# SilovaCastV2.net
KiCad netlist of a schematic drawn in EAGLE
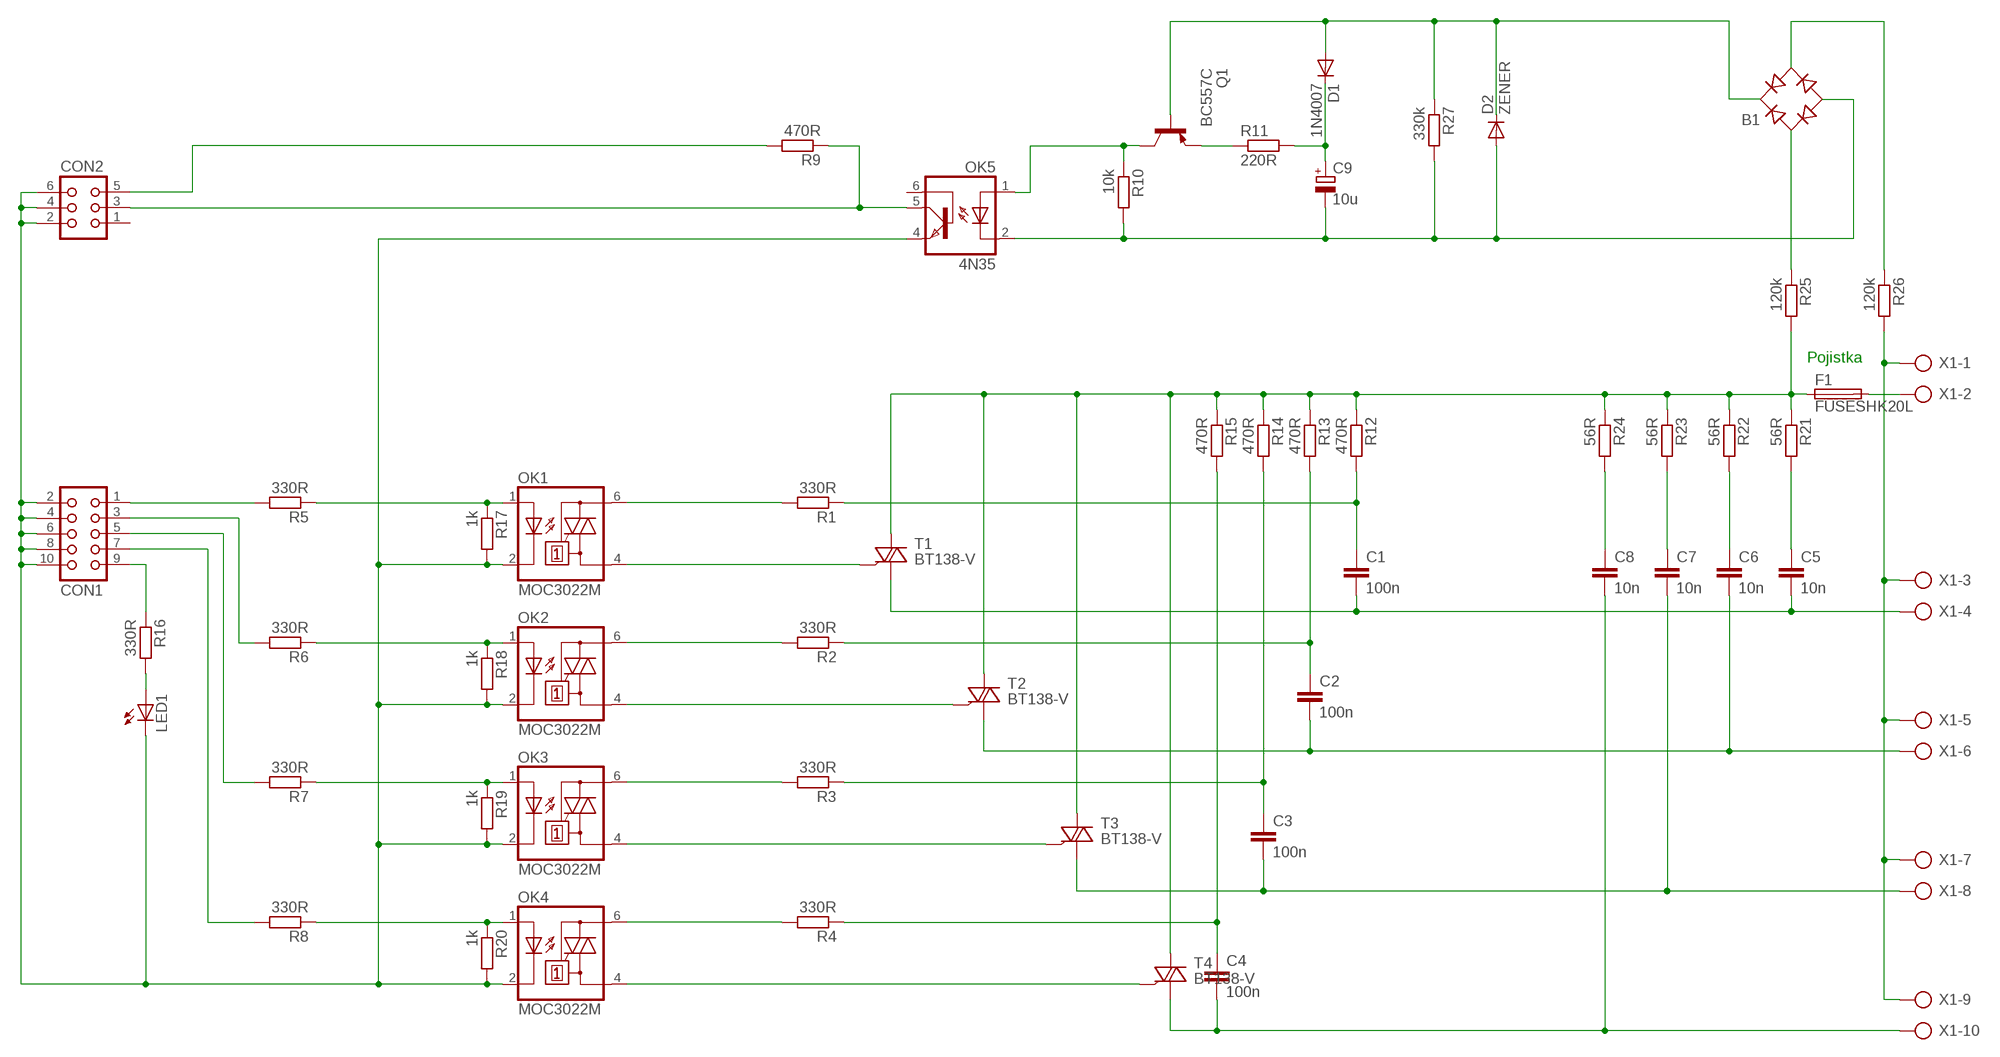
[diagram p0: schematic, sheet 1]

(export (version "E")
  (design (tool "Eeschema 10.0.6"))
  (components
    (comp (ref "B1")
      (value "RB1A")
      (footprint "eagle-import:RB1A")
      (libsource (lib "eagle-import") (part "RB1A"))
    )
    (comp (ref "C1")
      (value "100n")
      (footprint "eagle-import:C7.5B6")
      (libsource (lib "eagle-import") (part "C7.5/6"))
    )
    (comp (ref "C2")
      (value "100n")
      (footprint "eagle-import:C7.5B6")
      (libsource (lib "eagle-import") (part "C7.5/6"))
    )
    (comp (ref "C3")
      (value "100n")
      (footprint "eagle-import:C7.5B6")
      (libsource (lib "eagle-import") (part "C7.5/6"))
    )
    (comp (ref "C4")
      (value "100n")
      (footprint "eagle-import:C7.5B6")
      (libsource (lib "eagle-import") (part "C7.5/6"))
    )
    (comp (ref "C5")
      (value "10n")
      (footprint "eagle-import:C7.5B6")
      (libsource (lib "eagle-import") (part "C7.5/6"))
    )
    (comp (ref "C6")
      (value "10n")
      (footprint "eagle-import:C7.5B6")
      (libsource (lib "eagle-import") (part "C7.5/6"))
    )
    (comp (ref "C7")
      (value "10n")
      (footprint "eagle-import:C7.5B6")
      (libsource (lib "eagle-import") (part "C7.5/6"))
    )
    (comp (ref "C8")
      (value "10n")
      (footprint "eagle-import:C7.5B6")
      (libsource (lib "eagle-import") (part "C7.5/6"))
    )
    (comp (ref "C9")
      (value "10u")
      (footprint "eagle-import:E3,5-8")
      (libsource (lib "eagle-import") (part "CPOL-EUE3.5-8"))
    )
    (comp (ref "CON1")
      (value "CON10")
      (footprint "eagle-import:CON10")
      (libsource (lib "eagle-import") (part "CON10"))
    )
    (comp (ref "CON2")
      (value "CON06")
      (footprint "eagle-import:CON06")
      (libsource (lib "eagle-import") (part "CON06"))
    )
    (comp (ref "D1")
      (value "1N4007")
      (footprint "eagle-import:DO41-10")
      (libsource (lib "eagle-import") (part "1N4004"))
    )
    (comp (ref "D2")
      (value "ZENER")
      (footprint "eagle-import:DO41-10")
      (libsource (lib "eagle-import") (part "1N4004"))
    )
    (comp (ref "F1")
      (value "FUSESHK20L")
      (footprint "eagle-import:SHK20L")
      (libsource (lib "eagle-import") (part "FUSESHK20L"))
    )
    (comp (ref "LED1")
      (value "LED5MM")
      (footprint "eagle-import:LED5MM")
      (libsource (lib "eagle-import") (part "LED5MM"))
    )
    (comp (ref "OK1")
      (value "MOC3022M")
      (footprint "eagle-import:DIL06")
      (fields (field (name "MF") "FAIRCHILD SEMICONDUCTOR") (field (name "MPN") "MOC3022-M"))
      (libsource (lib "eagle-import") (part "MOC30M22"))
    )
    (comp (ref "OK2")
      (value "MOC3022M")
      (footprint "eagle-import:DIL06")
      (fields (field (name "MF") "FAIRCHILD SEMICONDUCTOR") (field (name "MPN") "MOC3022-M"))
      (libsource (lib "eagle-import") (part "MOC30M22"))
    )
    (comp (ref "OK3")
      (value "MOC3022M")
      (footprint "eagle-import:DIL06")
      (fields (field (name "MF") "FAIRCHILD SEMICONDUCTOR") (field (name "MPN") "MOC3022-M"))
      (libsource (lib "eagle-import") (part "MOC30M22"))
    )
    (comp (ref "OK4")
      (value "MOC3022M")
      (footprint "eagle-import:DIL06")
      (fields (field (name "MF") "FAIRCHILD SEMICONDUCTOR") (field (name "MPN") "MOC3022-M"))
      (libsource (lib "eagle-import") (part "MOC30M22"))
    )
    (comp (ref "OK5")
      (value "4N35")
      (footprint "eagle-import:DIL06")
      (fields (field (name "MF") "FAIRCHILD SEMICONDUCTOR"))
      (libsource (lib "eagle-import") (part "4N35"))
    )
    (comp (ref "Q1")
      (value "BC557C")
      (footprint "eagle-import:TO92-EBC")
      (libsource (lib "eagle-import") (part "BC557C"))
    )
    (comp (ref "R1")
      (value "330R")
      (footprint "eagle-import:0207_12")
      (libsource (lib "eagle-import") (part "R-EU_0207/12"))
    )
    (comp (ref "R2")
      (value "330R")
      (footprint "eagle-import:0207_12")
      (libsource (lib "eagle-import") (part "R-EU_0207/12"))
    )
    (comp (ref "R3")
      (value "330R")
      (footprint "eagle-import:0207_12")
      (libsource (lib "eagle-import") (part "R-EU_0207/12"))
    )
    (comp (ref "R4")
      (value "330R")
      (footprint "eagle-import:0207_12")
      (libsource (lib "eagle-import") (part "R-EU_0207/12"))
    )
    (comp (ref "R5")
      (value "330R")
      (footprint "eagle-import:R0805")
      (libsource (lib "eagle-import") (part "R-EU_R0805"))
    )
    (comp (ref "R6")
      (value "330R")
      (footprint "eagle-import:R0805")
      (libsource (lib "eagle-import") (part "R-EU_R0805"))
    )
    (comp (ref "R7")
      (value "330R")
      (footprint "eagle-import:R0805")
      (libsource (lib "eagle-import") (part "R-EU_R0805"))
    )
    (comp (ref "R8")
      (value "330R")
      (footprint "eagle-import:R0805")
      (libsource (lib "eagle-import") (part "R-EU_R0805"))
    )
    (comp (ref "R9")
      (value "470R")
      (footprint "eagle-import:0207_12")
      (libsource (lib "eagle-import") (part "R-EU_0207/12"))
    )
    (comp (ref "R10")
      (value "10k")
      (footprint "eagle-import:R0805")
      (libsource (lib "eagle-import") (part "R-EU_R0805"))
    )
    (comp (ref "R11")
      (value "220R")
      (footprint "eagle-import:0207_12")
      (libsource (lib "eagle-import") (part "R-EU_0207/12"))
    )
    (comp (ref "R12")
      (value "470R")
      (footprint "eagle-import:0207_12")
      (libsource (lib "eagle-import") (part "R-EU_0207/12"))
    )
    (comp (ref "R13")
      (value "470R")
      (footprint "eagle-import:0207_12")
      (libsource (lib "eagle-import") (part "R-EU_0207/12"))
    )
    (comp (ref "R14")
      (value "470R")
      (footprint "eagle-import:0207_12")
      (libsource (lib "eagle-import") (part "R-EU_0207/12"))
    )
    (comp (ref "R15")
      (value "470R")
      (footprint "eagle-import:0207_12")
      (libsource (lib "eagle-import") (part "R-EU_0207/12"))
    )
    (comp (ref "R16")
      (value "330R")
      (footprint "eagle-import:0207_12")
      (libsource (lib "eagle-import") (part "R-EU_0207/12"))
    )
    (comp (ref "R17")
      (value "1k")
      (footprint "eagle-import:R0805")
      (libsource (lib "eagle-import") (part "R-EU_R0805"))
    )
    (comp (ref "R18")
      (value "1k")
      (footprint "eagle-import:R0805")
      (libsource (lib "eagle-import") (part "R-EU_R0805"))
    )
    (comp (ref "R19")
      (value "1k")
      (footprint "eagle-import:R0805")
      (libsource (lib "eagle-import") (part "R-EU_R0805"))
    )
    (comp (ref "R20")
      (value "1k")
      (footprint "eagle-import:R0805")
      (libsource (lib "eagle-import") (part "R-EU_R0805"))
    )
    (comp (ref "R21")
      (value "56R")
      (footprint "eagle-import:0411_15")
      (libsource (lib "eagle-import") (part "R-EU_0411/15"))
    )
    (comp (ref "R22")
      (value "56R")
      (footprint "eagle-import:0411_15")
      (libsource (lib "eagle-import") (part "R-EU_0411/15"))
    )
    (comp (ref "R23")
      (value "56R")
      (footprint "eagle-import:0411_15")
      (libsource (lib "eagle-import") (part "R-EU_0411/15"))
    )
    (comp (ref "R24")
      (value "56R")
      (footprint "eagle-import:0411_15")
      (libsource (lib "eagle-import") (part "R-EU_0411/15"))
    )
    (comp (ref "R25")
      (value "120k")
      (footprint "eagle-import:0207_12")
      (libsource (lib "eagle-import") (part "R-EU_0207/12"))
    )
    (comp (ref "R26")
      (value "120k")
      (footprint "eagle-import:0207_12")
      (libsource (lib "eagle-import") (part "R-EU_0207/12"))
    )
    (comp (ref "R27")
      (value "330k")
      (footprint "eagle-import:0207_12")
      (libsource (lib "eagle-import") (part "R-EU_0207/12"))
    )
    (comp (ref "T1")
      (value "BT138-V")
      (footprint "eagle-import:TO220BV")
      (libsource (lib "eagle-import") (part "BT138-V"))
    )
    (comp (ref "T2")
      (value "BT138-V")
      (footprint "eagle-import:TO220BV")
      (libsource (lib "eagle-import") (part "BT138-V"))
    )
    (comp (ref "T3")
      (value "BT138-V")
      (footprint "eagle-import:TO220BV")
      (libsource (lib "eagle-import") (part "BT138-V"))
    )
    (comp (ref "T4")
      (value "BT138-V")
      (footprint "eagle-import:TO220BV")
      (libsource (lib "eagle-import") (part "BT138-V"))
    )
    (comp (ref "X1")
      (value "AK300/10")
      (footprint "eagle-import:AK300_10")
      (libsource (lib "eagle-import") (part "AK300/10"))
    )
  )
  (nets
    (net (code "1") (name "Net-(B1-Pad+)") (class "Default")
      (node (ref "B1") (pin "+") (pinfunction "+_+") (pintype "passive"))
      (node (ref "D1") (pin "A") (pinfunction "A_A") (pintype "passive"))
      (node (ref "D2") (pin "C") (pinfunction "C_C") (pintype "passive"))
      (node (ref "Q1") (pin "B") (pinfunction "B_B") (pintype "passive"))
      (node (ref "R27") (pin "1") (pinfunction "1_1") (pintype "passive"))
    )
    (net (code "2") (name "Net-(B1-PadAC1)") (class "Default")
      (node (ref "B1") (pin "AC1") (pinfunction "AC1_AC1") (pintype "passive"))
      (node (ref "R25") (pin "1") (pinfunction "1_1") (pintype "passive"))
    )
    (net (code "3") (name "Net-(B1-PadAC2)") (class "Default")
      (node (ref "B1") (pin "AC2") (pinfunction "AC2_AC2") (pintype "passive"))
      (node (ref "R26") (pin "1") (pinfunction "1_1") (pintype "passive"))
    )
    (net (code "4") (name "Net-(C1-Pad1)") (class "Default")
      (node (ref "C1") (pin "1") (pinfunction "1_1") (pintype "passive"))
      (node (ref "R1") (pin "1") (pinfunction "1_1") (pintype "passive"))
      (node (ref "R12") (pin "2") (pinfunction "2_2") (pintype "passive"))
    )
    (net (code "5") (name "Net-(C2-Pad1)") (class "Default")
      (node (ref "C2") (pin "1") (pinfunction "1_1") (pintype "passive"))
      (node (ref "R13") (pin "2") (pinfunction "2_2") (pintype "passive"))
      (node (ref "R2") (pin "1") (pinfunction "1_1") (pintype "passive"))
    )
    (net (code "6") (name "Net-(C3-Pad1)") (class "Default")
      (node (ref "C3") (pin "1") (pinfunction "1_1") (pintype "passive"))
      (node (ref "R14") (pin "2") (pinfunction "2_2") (pintype "passive"))
      (node (ref "R3") (pin "1") (pinfunction "1_1") (pintype "passive"))
    )
    (net (code "7") (name "Net-(C4-Pad1)") (class "Default")
      (node (ref "C4") (pin "1") (pinfunction "1_1") (pintype "passive"))
      (node (ref "R15") (pin "2") (pinfunction "2_2") (pintype "passive"))
      (node (ref "R4") (pin "1") (pinfunction "1_1") (pintype "passive"))
    )
    (net (code "8") (name "Net-(C5-Pad1)") (class "Default")
      (node (ref "C5") (pin "1") (pinfunction "1_1") (pintype "passive"))
      (node (ref "R21") (pin "2") (pinfunction "2_2") (pintype "passive"))
    )
    (net (code "9") (name "Net-(C6-Pad1)") (class "Default")
      (node (ref "C6") (pin "1") (pinfunction "1_1") (pintype "passive"))
      (node (ref "R22") (pin "2") (pinfunction "2_2") (pintype "passive"))
    )
    (net (code "10") (name "Net-(C7-Pad1)") (class "Default")
      (node (ref "C7") (pin "1") (pinfunction "1_1") (pintype "passive"))
      (node (ref "R23") (pin "2") (pinfunction "2_2") (pintype "passive"))
    )
    (net (code "11") (name "Net-(C8-Pad1)") (class "Default")
      (node (ref "C8") (pin "1") (pinfunction "1_1") (pintype "passive"))
      (node (ref "R24") (pin "2") (pinfunction "2_2") (pintype "passive"))
    )
    (net (code "12") (name "Net-(C9-Pad+)") (class "Default")
      (node (ref "C9") (pin "+") (pinfunction "+_+") (pintype "passive"))
      (node (ref "D1") (pin "C") (pinfunction "C_C") (pintype "passive"))
      (node (ref "R11") (pin "2") (pinfunction "2_2") (pintype "passive"))
    )
    (net (code "13") (name "Net-(CON1-Pad1)") (class "Default")
      (node (ref "CON1") (pin "1") (pinfunction "1_1") (pintype "passive"))
      (node (ref "R5") (pin "2") (pinfunction "2_2") (pintype "passive"))
    )
    (net (code "14") (name "Net-(CON1-Pad3)") (class "Default")
      (node (ref "CON1") (pin "3") (pinfunction "3_3") (pintype "passive"))
      (node (ref "R6") (pin "2") (pinfunction "2_2") (pintype "passive"))
    )
    (net (code "15") (name "Net-(CON1-Pad5)") (class "Default")
      (node (ref "CON1") (pin "5") (pinfunction "5_5") (pintype "passive"))
      (node (ref "R7") (pin "2") (pinfunction "2_2") (pintype "passive"))
    )
    (net (code "16") (name "Net-(CON1-Pad7)") (class "Default")
      (node (ref "CON1") (pin "7") (pinfunction "7_7") (pintype "passive"))
      (node (ref "R8") (pin "2") (pinfunction "2_2") (pintype "passive"))
    )
    (net (code "17") (name "Net-(CON1-Pad9)") (class "Default")
      (node (ref "CON1") (pin "9") (pinfunction "9_9") (pintype "passive"))
      (node (ref "R16") (pin "1") (pinfunction "1_1") (pintype "passive"))
    )
    (net (code "18") (name "Net-(CON2-Pad5)") (class "Default")
      (node (ref "CON2") (pin "5") (pinfunction "5_5") (pintype "passive"))
      (node (ref "R9") (pin "2") (pinfunction "2_2") (pintype "passive"))
    )
    (net (code "19") (name "Net-(F1-1)") (class "Default")
      (node (ref "F1") (pin "1A") (pinfunction "1_1A") (pintype "passive"))
      (node (ref "R12") (pin "1") (pinfunction "1_1") (pintype "passive"))
      (node (ref "R13") (pin "1") (pinfunction "1_1") (pintype "passive"))
      (node (ref "R14") (pin "1") (pinfunction "1_1") (pintype "passive"))
      (node (ref "R15") (pin "1") (pinfunction "1_1") (pintype "passive"))
      (node (ref "R21") (pin "1") (pinfunction "1_1") (pintype "passive"))
      (node (ref "R22") (pin "1") (pinfunction "1_1") (pintype "passive"))
      (node (ref "R23") (pin "1") (pinfunction "1_1") (pintype "passive"))
      (node (ref "R24") (pin "1") (pinfunction "1_1") (pintype "passive"))
      (node (ref "R25") (pin "2") (pinfunction "2_2") (pintype "passive"))
      (node (ref "T1") (pin "T2") (pinfunction "A2_T2") (pintype "passive"))
      (node (ref "T2") (pin "T2") (pinfunction "A2_T2") (pintype "passive"))
      (node (ref "T3") (pin "T2") (pinfunction "A2_T2") (pintype "passive"))
      (node (ref "T4") (pin "T2") (pinfunction "A2_T2") (pintype "passive"))
    )
    (net (code "20") (name "Net-(F1-2)") (class "Default")
      (node (ref "F1") (pin "2A") (pinfunction "2_2A") (pintype "passive"))
      (node (ref "X1") (pin "2") (pinfunction "KL_2") (pintype "passive"))
    )
    (net (code "21") (name "Net-(LED1-C)") (class "Default")
      (node (ref "CON1") (pin "10") (pinfunction "10_10") (pintype "passive"))
      (node (ref "CON1") (pin "2") (pinfunction "2_2") (pintype "passive"))
      (node (ref "CON1") (pin "4") (pinfunction "4_4") (pintype "passive"))
      (node (ref "CON1") (pin "6") (pinfunction "6_6") (pintype "passive"))
      (node (ref "CON1") (pin "8") (pinfunction "8_8") (pintype "passive"))
      (node (ref "CON2") (pin "2") (pinfunction "2_2") (pintype "passive"))
      (node (ref "CON2") (pin "4") (pinfunction "4_4") (pintype "passive"))
      (node (ref "CON2") (pin "6") (pinfunction "6_6") (pintype "passive"))
      (node (ref "LED1") (pin "K") (pinfunction "C_K") (pintype "passive"))
      (node (ref "OK1") (pin "2") (pinfunction "C_2") (pintype "passive"))
      (node (ref "OK2") (pin "2") (pinfunction "C_2") (pintype "passive"))
      (node (ref "OK3") (pin "2") (pinfunction "C_2") (pintype "passive"))
      (node (ref "OK4") (pin "2") (pinfunction "C_2") (pintype "passive"))
      (node (ref "OK5") (pin "4") (pinfunction "EMI_4") (pintype "passive"))
      (node (ref "R17") (pin "2") (pinfunction "2_2") (pintype "passive"))
      (node (ref "R18") (pin "2") (pinfunction "2_2") (pintype "passive"))
      (node (ref "R19") (pin "2") (pinfunction "2_2") (pintype "passive"))
      (node (ref "R20") (pin "2") (pinfunction "2_2") (pintype "passive"))
    )
    (net (code "22") (name "Net-(LED1-PadA)") (class "Default")
      (node (ref "LED1") (pin "A") (pinfunction "A_A") (pintype "passive"))
      (node (ref "R16") (pin "2") (pinfunction "2_2") (pintype "passive"))
    )
    (net (code "23") (name "Net-(OK1-A)") (class "Default")
      (node (ref "OK1") (pin "1") (pinfunction "A_1") (pintype "passive"))
      (node (ref "R17") (pin "1") (pinfunction "1_1") (pintype "passive"))
      (node (ref "R5") (pin "1") (pinfunction "1_1") (pintype "passive"))
    )
    (net (code "24") (name "Net-(OK1-A1)") (class "Default")
      (node (ref "OK1") (pin "4") (pinfunction "A1_4") (pintype "passive"))
      (node (ref "T1") (pin "G") (pinfunction "G_G") (pintype "passive"))
    )
    (net (code "25") (name "Net-(OK1-A2)") (class "Default")
      (node (ref "OK1") (pin "6") (pinfunction "A2_6") (pintype "passive"))
      (node (ref "R1") (pin "2") (pinfunction "2_2") (pintype "passive"))
    )
    (net (code "26") (name "Net-(OK2-A)") (class "Default")
      (node (ref "OK2") (pin "1") (pinfunction "A_1") (pintype "passive"))
      (node (ref "R18") (pin "1") (pinfunction "1_1") (pintype "passive"))
      (node (ref "R6") (pin "1") (pinfunction "1_1") (pintype "passive"))
    )
    (net (code "27") (name "Net-(OK2-A1)") (class "Default")
      (node (ref "OK2") (pin "4") (pinfunction "A1_4") (pintype "passive"))
      (node (ref "T2") (pin "G") (pinfunction "G_G") (pintype "passive"))
    )
    (net (code "28") (name "Net-(OK2-A2)") (class "Default")
      (node (ref "OK2") (pin "6") (pinfunction "A2_6") (pintype "passive"))
      (node (ref "R2") (pin "2") (pinfunction "2_2") (pintype "passive"))
    )
    (net (code "29") (name "Net-(OK3-A)") (class "Default")
      (node (ref "OK3") (pin "1") (pinfunction "A_1") (pintype "passive"))
      (node (ref "R19") (pin "1") (pinfunction "1_1") (pintype "passive"))
      (node (ref "R7") (pin "1") (pinfunction "1_1") (pintype "passive"))
    )
    (net (code "30") (name "Net-(OK3-A1)") (class "Default")
      (node (ref "OK3") (pin "4") (pinfunction "A1_4") (pintype "passive"))
      (node (ref "T3") (pin "G") (pinfunction "G_G") (pintype "passive"))
    )
    (net (code "31") (name "Net-(OK3-A2)") (class "Default")
      (node (ref "OK3") (pin "6") (pinfunction "A2_6") (pintype "passive"))
      (node (ref "R3") (pin "2") (pinfunction "2_2") (pintype "passive"))
    )
    (net (code "32") (name "Net-(OK4-A)") (class "Default")
      (node (ref "OK4") (pin "1") (pinfunction "A_1") (pintype "passive"))
      (node (ref "R20") (pin "1") (pinfunction "1_1") (pintype "passive"))
      (node (ref "R8") (pin "1") (pinfunction "1_1") (pintype "passive"))
    )
    (net (code "33") (name "Net-(OK4-A1)") (class "Default")
      (node (ref "OK4") (pin "4") (pinfunction "A1_4") (pintype "passive"))
      (node (ref "T4") (pin "G") (pinfunction "G_G") (pintype "passive"))
    )
    (net (code "34") (name "Net-(OK4-A2)") (class "Default")
      (node (ref "OK4") (pin "6") (pinfunction "A2_6") (pintype "passive"))
      (node (ref "R4") (pin "2") (pinfunction "2_2") (pintype "passive"))
    )
    (net (code "35") (name "Net-(OK5-A)") (class "Default")
      (node (ref "OK5") (pin "1") (pinfunction "A_1") (pintype "passive"))
      (node (ref "Q1") (pin "C") (pinfunction "C_C") (pintype "passive"))
      (node (ref "R10") (pin "1") (pinfunction "1_1") (pintype "passive"))
    )
    (net (code "36") (name "Net-(OK5-C)") (class "Default")
      (node (ref "B1") (pin "-") (pinfunction "-_-") (pintype "passive"))
      (node (ref "C9") (pin "-") (pinfunction "-_-") (pintype "passive"))
      (node (ref "D2") (pin "A") (pinfunction "A_A") (pintype "passive"))
      (node (ref "OK5") (pin "2") (pinfunction "C_2") (pintype "passive"))
      (node (ref "R10") (pin "2") (pinfunction "2_2") (pintype "passive"))
      (node (ref "R27") (pin "2") (pinfunction "2_2") (pintype "passive"))
    )
    (net (code "37") (name "Net-(OK5-COL)") (class "Default")
      (node (ref "CON2") (pin "3") (pinfunction "3_3") (pintype "passive"))
      (node (ref "OK5") (pin "5") (pinfunction "COL_5") (pintype "passive"))
      (node (ref "R9") (pin "1") (pinfunction "1_1") (pintype "passive"))
    )
    (net (code "38") (name "Net-(Q1-PadE)") (class "Default")
      (node (ref "Q1") (pin "E") (pinfunction "E_E") (pintype "passive"))
      (node (ref "R11") (pin "1") (pinfunction "1_1") (pintype "passive"))
    )
    (net (code "39") (name "Net-(T1-A1)") (class "Default")
      (node (ref "C1") (pin "2") (pinfunction "2_2") (pintype "passive"))
      (node (ref "C5") (pin "2") (pinfunction "2_2") (pintype "passive"))
      (node (ref "T1") (pin "T1") (pinfunction "A1_T1") (pintype "passive"))
      (node (ref "X1") (pin "4") (pinfunction "KL_4") (pintype "passive"))
    )
    (net (code "40") (name "Net-(T2-A1)") (class "Default")
      (node (ref "C2") (pin "2") (pinfunction "2_2") (pintype "passive"))
      (node (ref "C6") (pin "2") (pinfunction "2_2") (pintype "passive"))
      (node (ref "T2") (pin "T1") (pinfunction "A1_T1") (pintype "passive"))
      (node (ref "X1") (pin "6") (pinfunction "KL_6") (pintype "passive"))
    )
    (net (code "41") (name "Net-(T3-A1)") (class "Default")
      (node (ref "C3") (pin "2") (pinfunction "2_2") (pintype "passive"))
      (node (ref "C7") (pin "2") (pinfunction "2_2") (pintype "passive"))
      (node (ref "T3") (pin "T1") (pinfunction "A1_T1") (pintype "passive"))
      (node (ref "X1") (pin "8") (pinfunction "KL_8") (pintype "passive"))
    )
    (net (code "42") (name "Net-(T4-A1)") (class "Default")
      (node (ref "C4") (pin "2") (pinfunction "2_2") (pintype "passive"))
      (node (ref "C8") (pin "2") (pinfunction "2_2") (pintype "passive"))
      (node (ref "T4") (pin "T1") (pinfunction "A1_T1") (pintype "passive"))
      (node (ref "X1") (pin "10") (pinfunction "KL_10") (pintype "passive"))
    )
    (net (code "43") (name "Net-(X1A-KL)") (class "Default")
      (node (ref "R26") (pin "2") (pinfunction "2_2") (pintype "passive"))
      (node (ref "X1") (pin "1") (pinfunction "KL_1") (pintype "passive"))
      (node (ref "X1") (pin "3") (pinfunction "KL_3") (pintype "passive"))
      (node (ref "X1") (pin "5") (pinfunction "KL_5") (pintype "passive"))
      (node (ref "X1") (pin "7") (pinfunction "KL_7") (pintype "passive"))
      (node (ref "X1") (pin "9") (pinfunction "KL_9") (pintype "passive"))
    )
    (net (code "44") (name "unconnected-(CON2-Pad1)") (class "Default")
      (node (ref "CON2") (pin "1") (pinfunction "1_1") (pintype "passive"))
    )
    (net (code "45") (name "unconnected-(OK5-BAS-Pad6)") (class "Default")
      (node (ref "OK5") (pin "6") (pinfunction "BAS_6") (pintype "passive"))
    )
  )
)
